# Reprogrammable_Timer.net
KiCad netlist of a schematic drawn in Altium Designer
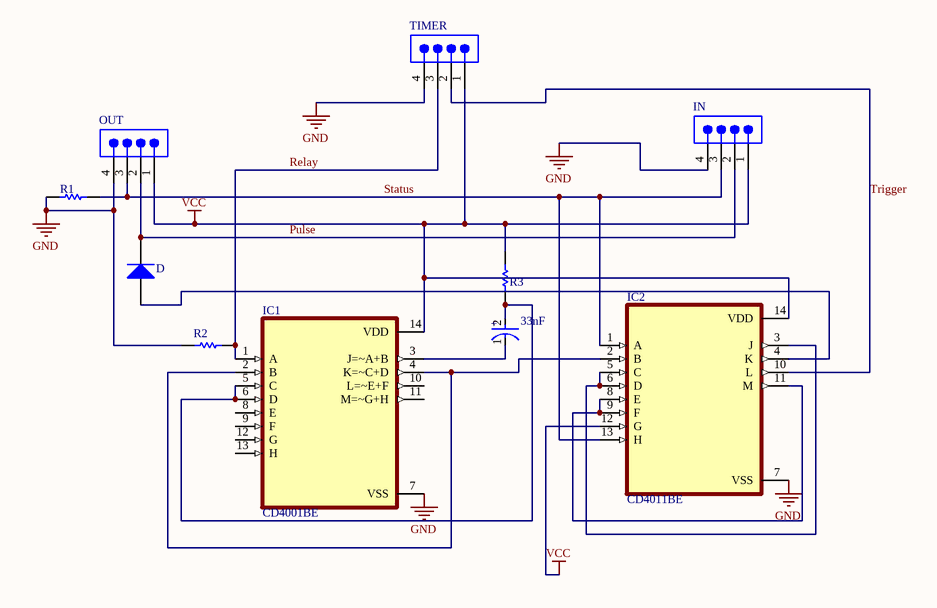
[diagram p0: Reprogrammable Timer.SchDoc]

(export (version "E")
  (design (tool "Eeschema 10.0.6"))
  (components
    (comp (ref "33nF")
      (value "EEUHD1H330")
      (footprint "FP-RAD-TH-D_5_0_5-L_11_1-MFG")
      (description "Aluminum Electrolytic Capacitors (Radial Lead Type) AEC-Q200 Qualified 33uF ±20% 50V")
      (fields (field (name "TOLERANCE") "20%") (field (name "VOLTAGE") "50V"))
      (libsource (lib "Altium Content Vault") (part "a00bbbee19879c290e62620ae7e47b1"))
    )
    (comp (ref "D")
      (value "1N4001-T")
      (footprint "DIOD-DO-41-P-2_V")
      (description "1.0 A Rectifier, 15 pF, 50 V, -65 to 150 degC, 2-Pin DO-41 Plastic, RoHS, Tape and Reel")
      (fields (field (name "MANUFACTURER") "Diodes Inc"))
      (libsource (lib "Altium Content Vault") (part "DIOD-D-A1K2-2"))
    )
    (comp (ref "IC1")
      (value "CD4001BE")
      (footprint "DIP794W45P254L1969H508Q14")
      (description "CMOS Quad 2-Input NOR Gate 14-PDIP -55 to 125")
      (fields (field (name "MF") "Texas Instruments"))
      (libsource (lib "CD4001BE") (part "CD4001BE"))
    )
    (comp (ref "IC2")
      (value "CD4011BE")
      (footprint "DIP794W45P254L1969H508Q14")
      (libsource (lib "CD4011BE") (part "CD4011BE"))
    )
    (comp (ref "IN")
      (value "TSW-104-08-L-S")
      (footprint "SMTC-TSW-104-08-X-S")
      (description "0.025\" SQ Post Header, Through-hole, Vertical, -55 to 125 degC, 2.54 mm Pitch, 4-Pin, Male, RoHS")
      (fields (field (name "MANUFACTURER") "Samtec"))
      (libsource (lib "Altium Content Vault") (part "SMTC-TSW-104-08-X-S"))
    )
    (comp (ref "OUT")
      (value "TSW-104-08-L-S")
      (footprint "SMTC-TSW-104-08-X-S")
      (description "0.025\" SQ Post Header, Through-hole, Vertical, -55 to 125 degC, 2.54 mm Pitch, 4-Pin, Male, RoHS")
      (fields (field (name "MANUFACTURER") "Samtec"))
      (libsource (lib "Altium Content Vault") (part "SMTC-TSW-104-08-X-S"))
    )
    (comp (ref "R1")
      (value "MFR-25FBF52-100K")
      (footprint "RESA60-630X240")
      (description "Axial Resistor, 100 KOhm, +/- 1%, 0.25 W, -55 to 155 degC, 2-Pin THD, RoHS, Bulk")
      (fields (field (name "TOLERANCE") "1%"))
      (libsource (lib "Altium Content Vault") (part "RES-2"))
    )
    (comp (ref "R2")
      (value "MFR-25FBF52-100K")
      (footprint "RESA60-630X240")
      (description "Axial Resistor, 100 KOhm, +/- 1%, 0.25 W, -55 to 155 degC, 2-Pin THD, RoHS, Bulk")
      (fields (field (name "TOLERANCE") "1%"))
      (libsource (lib "Altium Content Vault") (part "RES-2"))
    )
    (comp (ref "R3")
      (value "MFR-25FBF52-100K")
      (footprint "RESA60-630X240")
      (description "Axial Resistor, 100 KOhm, +/- 1%, 0.25 W, -55 to 155 degC, 2-Pin THD, RoHS, Bulk")
      (fields (field (name "TOLERANCE") "1%"))
      (libsource (lib "Altium Content Vault") (part "RES-2"))
    )
    (comp (ref "TIMER")
      (value "TSW-104-08-L-S")
      (footprint "SMTC-TSW-104-08-X-S")
      (description "0.025\" SQ Post Header, Through-hole, Vertical, -55 to 125 degC, 2.54 mm Pitch, 4-Pin, Male, RoHS")
      (fields (field (name "MANUFACTURER") "Samtec"))
      (libsource (lib "Altium Content Vault") (part "SMTC-TSW-104-08-X-S"))
    )
  )
  (nets
    (net (code "1") (name "/Pulse") (class "Default")
      (node (ref "D") (pin "2") (pinfunction "K_2") (pintype "passive"))
      (node (ref "IN") (pin "2") (pinfunction "2_2") (pintype "passive"))
      (node (ref "OUT") (pin "2") (pinfunction "2_2") (pintype "passive"))
    )
    (net (code "2") (name "/Relay") (class "Default")
      (node (ref "IC1") (pin "1") (pinfunction "A_1") (pintype "input"))
      (node (ref "R2") (pin "2") (pinfunction "2_2") (pintype "passive"))
      (node (ref "TIMER") (pin "3") (pinfunction "3_3") (pintype "passive"))
    )
    (net (code "3") (name "/Status") (class "Default")
      (node (ref "IC2") (pin "1") (pinfunction "A_1") (pintype "input"))
      (node (ref "IC2") (pin "13") (pinfunction "H_13") (pintype "input"))
      (node (ref "IN") (pin "3") (pinfunction "3_3") (pintype "passive"))
      (node (ref "OUT") (pin "3") (pinfunction "3_3") (pintype "passive"))
      (node (ref "R1") (pin "1") (pinfunction "1_1") (pintype "passive"))
    )
    (net (code "4") (name "/Trigger") (class "Default")
      (node (ref "IC2") (pin "10") (pinfunction "L_10") (pintype "output"))
      (node (ref "TIMER") (pin "2") (pinfunction "2_2") (pintype "passive"))
    )
    (net (code "5") (name "GND") (class "Default")
      (node (ref "IC1") (pin "7") (pinfunction "VSS_7") (pintype "power_in"))
      (node (ref "IC2") (pin "7") (pinfunction "VSS_7") (pintype "power_in"))
      (node (ref "IN") (pin "4") (pinfunction "4_4") (pintype "passive"))
      (node (ref "OUT") (pin "4") (pinfunction "4_4") (pintype "passive"))
      (node (ref "R1") (pin "2") (pinfunction "2_2") (pintype "passive"))
      (node (ref "R2") (pin "1") (pinfunction "1_1") (pintype "passive"))
      (node (ref "TIMER") (pin "4") (pinfunction "4_4") (pintype "passive"))
    )
    (net (code "6") (name "Net-(33nF-A)") (class "Default")
      (node (ref "33nF") (pin "2") (pinfunction "A_2") (pintype "passive"))
      (node (ref "IC1") (pin "5") (pinfunction "C_5") (pintype "input"))
      (node (ref "IC1") (pin "6") (pinfunction "D_6") (pintype "input"))
      (node (ref "R3") (pin "1") (pinfunction "1_1") (pintype "passive"))
    )
    (net (code "7") (name "Net-(33nF-C)") (class "Default")
      (node (ref "33nF") (pin "1") (pinfunction "C_1") (pintype "passive"))
      (node (ref "IC1") (pin "3") (pinfunction "J=~A+B_3") (pintype "output"))
    )
    (net (code "8") (name "Net-(D-A)") (class "Default")
      (node (ref "D") (pin "1") (pinfunction "A_1") (pintype "passive"))
      (node (ref "IC2") (pin "4") (pinfunction "K_4") (pintype "output"))
    )
    (net (code "9") (name "Net-(IC1-B)") (class "Default")
      (node (ref "IC1") (pin "2") (pinfunction "B_2") (pintype "input"))
      (node (ref "IC1") (pin "4") (pinfunction "K=~C+D_4") (pintype "output"))
      (node (ref "IC2") (pin "2") (pinfunction "B_2") (pintype "input"))
    )
    (net (code "10") (name "Net-(IC2-C)") (class "Default")
      (node (ref "IC2") (pin "3") (pinfunction "J_3") (pintype "output"))
      (node (ref "IC2") (pin "5") (pinfunction "C_5") (pintype "input"))
      (node (ref "IC2") (pin "6") (pinfunction "D_6") (pintype "input"))
    )
    (net (code "11") (name "Net-(IC2-E)") (class "Default")
      (node (ref "IC2") (pin "11") (pinfunction "M_11") (pintype "output"))
      (node (ref "IC2") (pin "8") (pinfunction "E_8") (pintype "input"))
      (node (ref "IC2") (pin "9") (pinfunction "F_9") (pintype "input"))
    )
    (net (code "12") (name "VCC") (class "Default")
      (node (ref "IC1") (pin "14") (pinfunction "VDD_14") (pintype "power_in"))
      (node (ref "IC2") (pin "12") (pinfunction "G_12") (pintype "input"))
      (node (ref "IC2") (pin "14") (pinfunction "VDD_14") (pintype "power_in"))
      (node (ref "IN") (pin "1") (pinfunction "1_1") (pintype "passive"))
      (node (ref "OUT") (pin "1") (pinfunction "1_1") (pintype "passive"))
      (node (ref "R3") (pin "2") (pinfunction "2_2") (pintype "passive"))
      (node (ref "TIMER") (pin "1") (pinfunction "1_1") (pintype "passive"))
    )
    (net (code "13") (name "unconnected-(IC1-E-Pad8)") (class "Default")
      (node (ref "IC1") (pin "8") (pinfunction "E_8") (pintype "input"))
    )
    (net (code "14") (name "unconnected-(IC1-F-Pad9)") (class "Default")
      (node (ref "IC1") (pin "9") (pinfunction "F_9") (pintype "input"))
    )
    (net (code "15") (name "unconnected-(IC1-G-Pad12)") (class "Default")
      (node (ref "IC1") (pin "12") (pinfunction "G_12") (pintype "input"))
    )
    (net (code "16") (name "unconnected-(IC1-H-Pad13)") (class "Default")
      (node (ref "IC1") (pin "13") (pinfunction "H_13") (pintype "input"))
    )
    (net (code "17") (name "unconnected-(IC1-L=~E+F-Pad10)") (class "Default")
      (node (ref "IC1") (pin "10") (pinfunction "L=~E+F_10") (pintype "output"))
    )
    (net (code "18") (name "unconnected-(IC1-M=~G+H-Pad11)") (class "Default")
      (node (ref "IC1") (pin "11") (pinfunction "M=~G+H_11") (pintype "output"))
    )
  )
)
